# SCH_Esp32-Wroom-Air-suspension_2025-01-0.net
KiCad netlist of a schematic drawn in EasyEDA
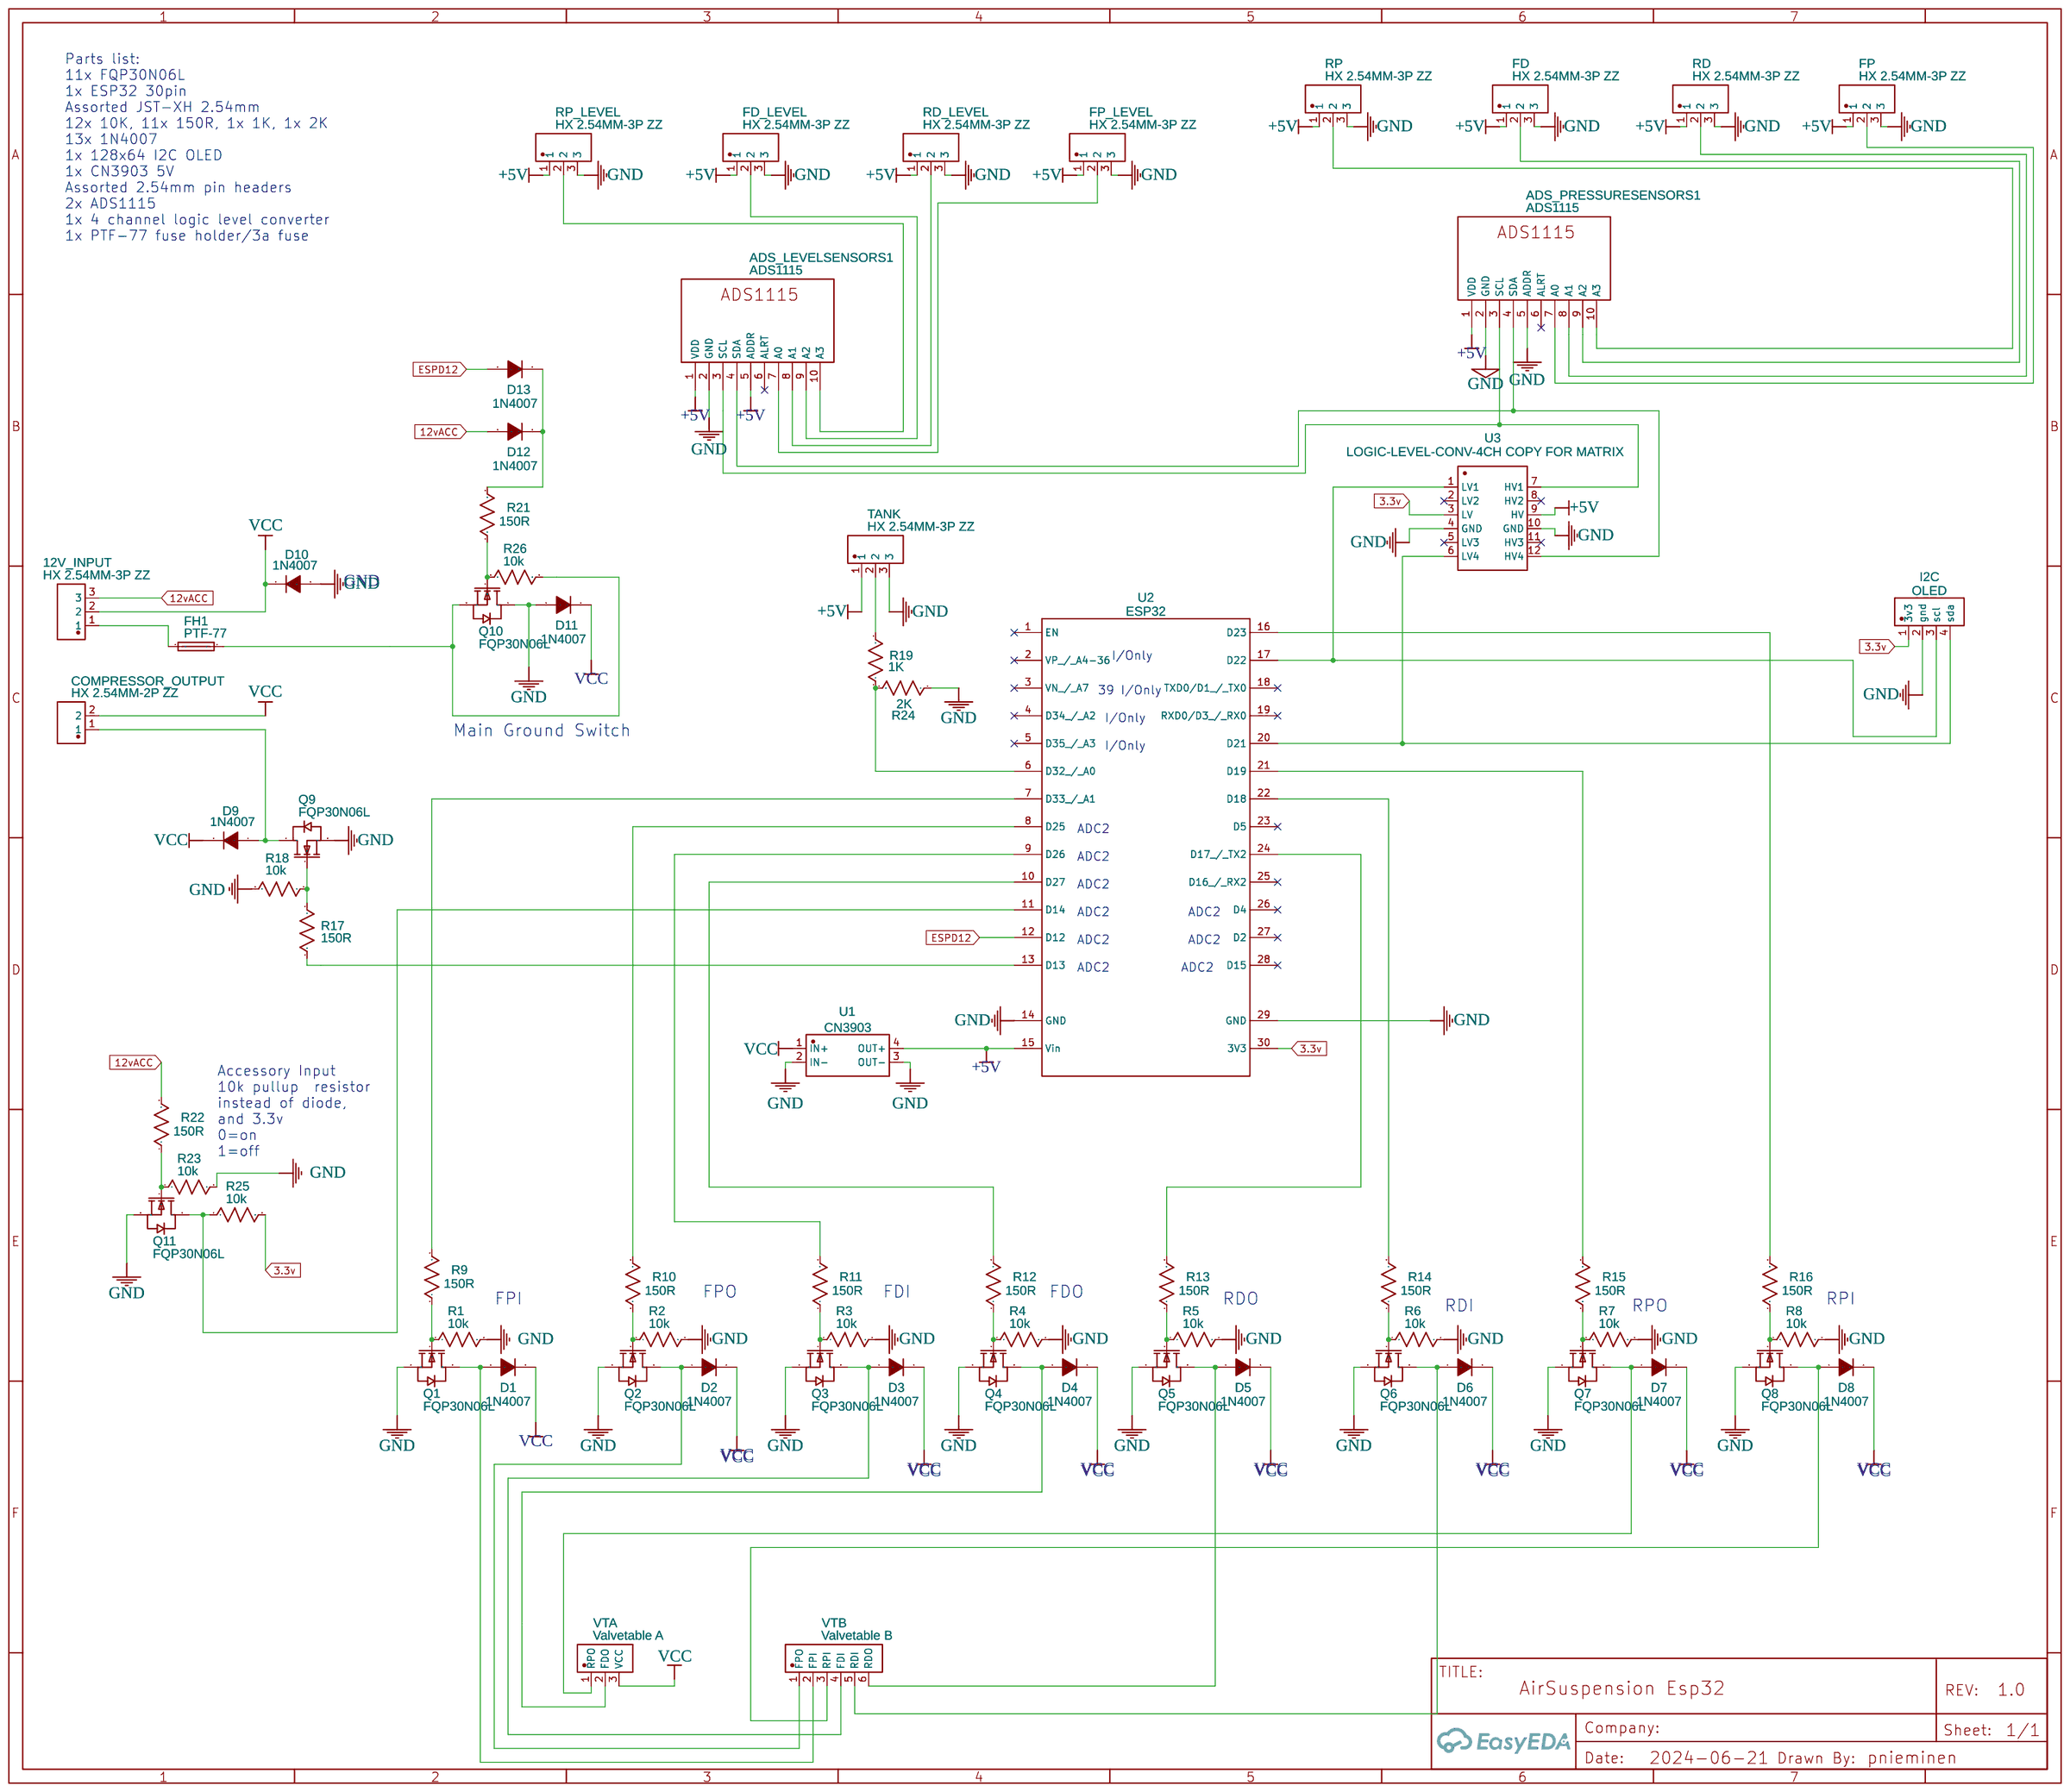
[diagram p0: schematic sheet]

(export (version "E")
  (design (tool "Eeschema 10.0.6"))
  (components
    (comp (ref "12V_INPUT")
      (value "HX 2.54MM-3P ZZ")
      (fields (field (name "Manufacturer Part") "HX 2.54mm-3P ZZ") (field (name "Manufacturer") "hanxia(韩下)"))
      (libsource (lib "") (part "HX 2.54MM-3P ZZ_9"))
    )
    (comp (ref "ADS_LEVELSENSORS1") (value "ADS1115") (libsource (lib "") (part "ADS1115_1")))
    (comp (ref "ADS_PRESSURESENSORS1") (value "ADS1115") (libsource (lib "") (part "ADS1115")))
    (comp (ref "COMPRESSOR_OUTPUT")
      (value "HX 2.54MM-2P ZZ")
      (fields (field (name "Manufacturer Part") "HX 2.54mm-2P ZZ") (field (name "Manufacturer") "hanxia(韩下)"))
      (libsource (lib "") (part "HX 2.54MM-2P ZZ"))
    )
    (comp (ref "D1")
      (value "1N4007")
      (fields (field (name "Manufacturer Part") "1N4007-E3/54") (field (name "Manufacturer") "VISHAY"))
      (libsource (lib "") (part "1N4007-E3/54"))
    )
    (comp (ref "D2")
      (value "1N4007")
      (fields (field (name "Manufacturer Part") "1N4007-E3/54") (field (name "Manufacturer") "VISHAY"))
      (libsource (lib "") (part "1N4007-E3/54"))
    )
    (comp (ref "D3")
      (value "1N4007")
      (fields (field (name "Manufacturer Part") "1N4007-E3/54") (field (name "Manufacturer") "VISHAY"))
      (libsource (lib "") (part "1N4007-E3/54"))
    )
    (comp (ref "D4")
      (value "1N4007")
      (fields (field (name "Manufacturer Part") "1N4007-E3/54") (field (name "Manufacturer") "VISHAY"))
      (libsource (lib "") (part "1N4007-E3/54"))
    )
    (comp (ref "D5")
      (value "1N4007")
      (fields (field (name "Manufacturer Part") "1N4007-E3/54") (field (name "Manufacturer") "VISHAY"))
      (libsource (lib "") (part "1N4007-E3/54"))
    )
    (comp (ref "D6")
      (value "1N4007")
      (fields (field (name "Manufacturer Part") "1N4007-E3/54") (field (name "Manufacturer") "VISHAY"))
      (libsource (lib "") (part "1N4007-E3/54"))
    )
    (comp (ref "D7")
      (value "1N4007")
      (fields (field (name "Manufacturer Part") "1N4007-E3/54") (field (name "Manufacturer") "VISHAY"))
      (libsource (lib "") (part "1N4007-E3/54"))
    )
    (comp (ref "D8")
      (value "1N4007")
      (fields (field (name "Manufacturer Part") "1N4007-E3/54") (field (name "Manufacturer") "VISHAY"))
      (libsource (lib "") (part "1N4007-E3/54"))
    )
    (comp (ref "D9")
      (value "1N4007")
      (fields (field (name "Manufacturer Part") "1N4007-E3/54") (field (name "Manufacturer") "VISHAY"))
      (libsource (lib "") (part "1N4007-E3/54_1"))
    )
    (comp (ref "D10")
      (value "1N4007")
      (fields (field (name "Manufacturer Part") "1N4007-E3/54") (field (name "Manufacturer") "VISHAY"))
      (libsource (lib "") (part "1N4007-E3/54_1"))
    )
    (comp (ref "D11")
      (value "1N4007")
      (fields (field (name "Manufacturer Part") "1N4007-E3/54") (field (name "Manufacturer") "VISHAY"))
      (libsource (lib "") (part "1N4007-E3/54"))
    )
    (comp (ref "D12")
      (value "1N4007")
      (fields (field (name "Manufacturer Part") "1N4007-E3/54") (field (name "Manufacturer") "VISHAY"))
      (libsource (lib "") (part "1N4007-E3/54"))
    )
    (comp (ref "D13")
      (value "1N4007")
      (fields (field (name "Manufacturer Part") "1N4007-E3/54") (field (name "Manufacturer") "VISHAY"))
      (libsource (lib "") (part "1N4007-E3/54"))
    )
    (comp (ref "FD")
      (value "HX 2.54MM-3P ZZ")
      (fields (field (name "Manufacturer Part") "HX 2.54mm-3P ZZ") (field (name "Manufacturer") "hanxia(韩下)"))
      (libsource (lib "") (part "HX 2.54MM-3P ZZ_3"))
    )
    (comp (ref "FD_LEVEL")
      (value "HX 2.54MM-3P ZZ")
      (fields (field (name "Manufacturer Part") "HX 2.54mm-3P ZZ") (field (name "Manufacturer") "hanxia(韩下)"))
      (libsource (lib "") (part "HX 2.54MM-3P ZZ_7"))
    )
    (comp (ref "FH1")
      (value "PTF-77")
      (fields (field (name "Manufacturer") "XFCN(兴飞)"))
      (libsource (lib "") (part "PTF-77"))
    )
    (comp (ref "FP")
      (value "HX 2.54MM-3P ZZ")
      (fields (field (name "Manufacturer Part") "HX 2.54mm-3P ZZ") (field (name "Manufacturer") "hanxia(韩下)"))
      (libsource (lib "") (part "HX 2.54MM-3P ZZ_1"))
    )
    (comp (ref "FP_LEVEL")
      (value "HX 2.54MM-3P ZZ")
      (fields (field (name "Manufacturer Part") "HX 2.54mm-3P ZZ") (field (name "Manufacturer") "hanxia(韩下)"))
      (libsource (lib "") (part "HX 2.54MM-3P ZZ_5"))
    )
    (comp (ref "OLED")
      (value "I2C")
      (fields (field (name "Manufacturer Part") "HX 2.54mm-4P ZZ") (field (name "Manufacturer") "hanxia(韩下)"))
      (libsource (lib "") (part "HX 2.54MM-4P ZZ"))
    )
    (comp (ref "Q1")
      (value "FQP30N06L")
      (fields (field (name "Manufacturer Part") "FQP30N06L-VB") (field (name "Manufacturer") "VBsemi(微碧半导体)"))
      (libsource (lib "") (part "FQP30N06L"))
    )
    (comp (ref "Q2")
      (value "FQP30N06L")
      (fields (field (name "Manufacturer Part") "FQP30N06L-VB") (field (name "Manufacturer") "VBsemi(微碧半导体)"))
      (libsource (lib "") (part "FQP30N06L"))
    )
    (comp (ref "Q3")
      (value "FQP30N06L")
      (fields (field (name "Manufacturer Part") "FQP30N06L-VB") (field (name "Manufacturer") "VBsemi(微碧半导体)"))
      (libsource (lib "") (part "FQP30N06L"))
    )
    (comp (ref "Q4")
      (value "FQP30N06L")
      (fields (field (name "Manufacturer Part") "FQP30N06L-VB") (field (name "Manufacturer") "VBsemi(微碧半导体)"))
      (libsource (lib "") (part "FQP30N06L"))
    )
    (comp (ref "Q5")
      (value "FQP30N06L")
      (fields (field (name "Manufacturer Part") "FQP30N06L-VB") (field (name "Manufacturer") "VBsemi(微碧半导体)"))
      (libsource (lib "") (part "FQP30N06L"))
    )
    (comp (ref "Q6")
      (value "FQP30N06L")
      (fields (field (name "Manufacturer Part") "FQP30N06L-VB") (field (name "Manufacturer") "VBsemi(微碧半导体)"))
      (libsource (lib "") (part "FQP30N06L"))
    )
    (comp (ref "Q7")
      (value "FQP30N06L")
      (fields (field (name "Manufacturer Part") "FQP30N06L-VB") (field (name "Manufacturer") "VBsemi(微碧半导体)"))
      (libsource (lib "") (part "FQP30N06L"))
    )
    (comp (ref "Q8")
      (value "FQP30N06L")
      (fields (field (name "Manufacturer Part") "FQP30N06L-VB") (field (name "Manufacturer") "VBsemi(微碧半导体)"))
      (libsource (lib "") (part "FQP30N06L"))
    )
    (comp (ref "Q9")
      (value "FQP30N06L")
      (fields (field (name "Manufacturer Part") "FQP30N06L-VB") (field (name "Manufacturer") "VBsemi(微碧半导体)"))
      (libsource (lib "") (part "FQP30N06L_1"))
    )
    (comp (ref "Q10")
      (value "FQP30N06L")
      (fields (field (name "Manufacturer Part") "FQP30N06L-VB") (field (name "Manufacturer") "VBsemi(微碧半导体)"))
      (libsource (lib "") (part "FQP30N06L"))
    )
    (comp (ref "Q11")
      (value "FQP30N06L")
      (fields (field (name "Manufacturer Part") "FQP30N06L-VB") (field (name "Manufacturer") "VBsemi(微碧半导体)"))
      (libsource (lib "") (part "FQP30N06L"))
    )
    (comp (ref "R1") (value "10k") (libsource (lib "") (part "R_AXIAL-1.0_US_1")))
    (comp (ref "R2") (value "10k") (libsource (lib "") (part "R_AXIAL-1.0_US_1")))
    (comp (ref "R3") (value "10k") (libsource (lib "") (part "R_AXIAL-1.0_US_1")))
    (comp (ref "R4") (value "10k") (libsource (lib "") (part "R_AXIAL-1.0_US_1")))
    (comp (ref "R5") (value "10k") (libsource (lib "") (part "R_AXIAL-1.0_US_1")))
    (comp (ref "R6") (value "10k") (libsource (lib "") (part "R_AXIAL-1.0_US_1")))
    (comp (ref "R7") (value "10k") (libsource (lib "") (part "R_AXIAL-1.0_US_1")))
    (comp (ref "R8") (value "10k") (libsource (lib "") (part "R_AXIAL-1.0_US_1")))
    (comp (ref "R9") (value "150R") (libsource (lib "") (part "R_AXIAL-1.0_US")))
    (comp (ref "R10") (value "150R") (libsource (lib "") (part "R_AXIAL-1.0_US")))
    (comp (ref "R11") (value "150R") (libsource (lib "") (part "R_AXIAL-1.0_US")))
    (comp (ref "R12") (value "150R") (libsource (lib "") (part "R_AXIAL-1.0_US")))
    (comp (ref "R13") (value "150R") (libsource (lib "") (part "R_AXIAL-1.0_US")))
    (comp (ref "R14") (value "150R") (libsource (lib "") (part "R_AXIAL-1.0_US")))
    (comp (ref "R15") (value "150R") (libsource (lib "") (part "R_AXIAL-1.0_US")))
    (comp (ref "R16") (value "150R") (libsource (lib "") (part "R_AXIAL-1.0_US")))
    (comp (ref "R17") (value "150R") (libsource (lib "") (part "R_AXIAL-1.0_US_3")))
    (comp (ref "R18") (value "10k") (libsource (lib "") (part "R_AXIAL-1.0_US_2")))
    (comp (ref "R19") (value "1K") (libsource (lib "") (part "R_AXIAL-1.0_US")))
    (comp (ref "R21") (value "150R") (libsource (lib "") (part "R_AXIAL-1.0_US")))
    (comp (ref "R22") (value "150R") (libsource (lib "") (part "R_AXIAL-1.0_US")))
    (comp (ref "R23") (value "10k") (libsource (lib "") (part "R_AXIAL-1.0_US_1")))
    (comp (ref "R24") (value "2K") (libsource (lib "") (part "R_AXIAL-1.0_US_2")))
    (comp (ref "R25") (value "10k") (libsource (lib "") (part "R_AXIAL-1.0_US_1")))
    (comp (ref "R26") (value "10k") (libsource (lib "") (part "R_AXIAL-1.0_US_1")))
    (comp (ref "RD")
      (value "HX 2.54MM-3P ZZ")
      (fields (field (name "Manufacturer Part") "HX 2.54mm-3P ZZ") (field (name "Manufacturer") "hanxia(韩下)"))
      (libsource (lib "") (part "HX 2.54MM-3P ZZ"))
    )
    (comp (ref "RD_LEVEL")
      (value "HX 2.54MM-3P ZZ")
      (fields (field (name "Manufacturer Part") "HX 2.54mm-3P ZZ") (field (name "Manufacturer") "hanxia(韩下)"))
      (libsource (lib "") (part "HX 2.54MM-3P ZZ_8"))
    )
    (comp (ref "RP")
      (value "HX 2.54MM-3P ZZ")
      (fields (field (name "Manufacturer Part") "HX 2.54mm-3P ZZ") (field (name "Manufacturer") "hanxia(韩下)"))
      (libsource (lib "") (part "HX 2.54MM-3P ZZ_6"))
    )
    (comp (ref "RP_LEVEL")
      (value "HX 2.54MM-3P ZZ")
      (fields (field (name "Manufacturer Part") "HX 2.54mm-3P ZZ") (field (name "Manufacturer") "hanxia(韩下)"))
      (libsource (lib "") (part "HX 2.54MM-3P ZZ_10"))
    )
    (comp (ref "TANK")
      (value "HX 2.54MM-3P ZZ")
      (fields (field (name "Manufacturer Part") "HX 2.54mm-3P ZZ") (field (name "Manufacturer") "hanxia(韩下)"))
      (libsource (lib "") (part "HX 2.54MM-3P ZZ_2"))
    )
    (comp (ref "U1") (value "CN3903") (libsource (lib "") (part "CN3903-DCDC-STEPDOWN-3V3")))
    (comp (ref "U2")
      (value "ESP32")
      (fields
        (field (name "Manufacturer Part") "ESP32WROOM32")
        (field (name "Manufacturer") "Espressif Systems")
      )
      (libsource (lib "") (part "ESP32"))
    )
    (comp (ref "U3")
      (value "LOGIC-LEVEL-CONV-4CH COPY FOR MATRIX")
      (fields (field (name "Manufacturer Part") "Level Converter 4"))
      (libsource (lib "") (part "LOGIC-LEVEL-CONV-4CH COPY FOR MATRIX"))
    )
    (comp (ref "VTA")
      (value "Valvetable A")
      (fields (field (name "Manufacturer Part") "HX 2.54mm-3P ZZ") (field (name "Manufacturer") "hanxia(韩下)"))
      (libsource (lib "") (part "HX 2.54MM-3P ZZ_4"))
    )
    (comp (ref "VTB")
      (value "Valvetable B")
      (fields (field (name "Manufacturer Part") "HX 2.54mm-6P ZZ") (field (name "Manufacturer") "hanxia(韩下)"))
      (libsource (lib "") (part "HX 2.54MM-6P ZZ"))
    )
  )
  (nets
    (net (code "1") (name "+5V") (class "Default")
      (node (ref "ADS_LEVELSENSORS1") (pin "1") (pinfunction "VDD_1") (pintype "unspecified"))
      (node (ref "ADS_LEVELSENSORS1") (pin "5") (pinfunction "ADDR_5") (pintype "unspecified"))
      (node (ref "ADS_PRESSURESENSORS1") (pin "1") (pinfunction "VDD_1") (pintype "unspecified"))
      (node (ref "FD") (pin "1") (pinfunction "1_1") (pintype "unspecified"))
      (node (ref "FD_LEVEL") (pin "1") (pinfunction "1_1") (pintype "unspecified"))
      (node (ref "FP") (pin "1") (pinfunction "1_1") (pintype "unspecified"))
      (node (ref "FP_LEVEL") (pin "1") (pinfunction "1_1") (pintype "unspecified"))
      (node (ref "RD") (pin "1") (pinfunction "1_1") (pintype "unspecified"))
      (node (ref "RD_LEVEL") (pin "1") (pinfunction "1_1") (pintype "unspecified"))
      (node (ref "RP") (pin "1") (pinfunction "1_1") (pintype "unspecified"))
      (node (ref "RP_LEVEL") (pin "1") (pinfunction "1_1") (pintype "unspecified"))
      (node (ref "TANK") (pin "1") (pinfunction "1_1") (pintype "unspecified"))
      (node (ref "U1") (pin "4") (pinfunction "OUT+_4") (pintype "unspecified"))
      (node (ref "U2") (pin "15") (pinfunction "Vin_15") (pintype "unspecified"))
      (node (ref "U3") (pin "9") (pinfunction "HV_9") (pintype "unspecified"))
    )
    (net (code "2") (name "3.3v") (class "Default")
      (node (ref "OLED") (pin "1") (pinfunction "3v3_1") (pintype "unspecified"))
      (node (ref "R25") (pin "2") (pinfunction "2_2") (pintype "unspecified"))
      (node (ref "U2") (pin "30") (pinfunction "3V3_30") (pintype "unspecified"))
      (node (ref "U3") (pin "3") (pinfunction "LV_3") (pintype "unspecified"))
    )
    (net (code "3") (name "12vACC") (class "Default")
      (node (ref "12V_INPUT") (pin "3") (pinfunction "3_3") (pintype "unspecified"))
      (node (ref "D12") (pin "1") (pinfunction "A_1") (pintype "unspecified"))
      (node (ref "R22") (pin "2") (pinfunction "2_2") (pintype "unspecified"))
    )
    (net (code "4") (name "ESPD12") (class "Default")
      (node (ref "D13") (pin "1") (pinfunction "A_1") (pintype "unspecified"))
      (node (ref "U2") (pin "12") (pinfunction "D12_12") (pintype "unspecified"))
    )
    (net (code "5") (name "GND") (class "Default")
      (node (ref "ADS_LEVELSENSORS1") (pin "2") (pinfunction "GND_2") (pintype "unspecified"))
      (node (ref "ADS_PRESSURESENSORS1") (pin "2") (pinfunction "GND_2") (pintype "unspecified"))
      (node (ref "ADS_PRESSURESENSORS1") (pin "5") (pinfunction "ADDR_5") (pintype "unspecified"))
      (node (ref "D10") (pin "1") (pinfunction "A_1") (pintype "unspecified"))
      (node (ref "D11") (pin "1") (pinfunction "A_1") (pintype "unspecified"))
      (node (ref "FD") (pin "3") (pinfunction "3_3") (pintype "unspecified"))
      (node (ref "FD_LEVEL") (pin "3") (pinfunction "3_3") (pintype "unspecified"))
      (node (ref "FP") (pin "3") (pinfunction "3_3") (pintype "unspecified"))
      (node (ref "FP_LEVEL") (pin "3") (pinfunction "3_3") (pintype "unspecified"))
      (node (ref "OLED") (pin "2") (pinfunction "gnd_2") (pintype "unspecified"))
      (node (ref "Q1") (pin "3") (pinfunction "S_3") (pintype "unspecified"))
      (node (ref "Q10") (pin "2") (pinfunction "D_2") (pintype "unspecified"))
      (node (ref "Q11") (pin "3") (pinfunction "S_3") (pintype "unspecified"))
      (node (ref "Q2") (pin "3") (pinfunction "S_3") (pintype "unspecified"))
      (node (ref "Q3") (pin "3") (pinfunction "S_3") (pintype "unspecified"))
      (node (ref "Q4") (pin "3") (pinfunction "S_3") (pintype "unspecified"))
      (node (ref "Q5") (pin "3") (pinfunction "S_3") (pintype "unspecified"))
      (node (ref "Q6") (pin "3") (pinfunction "S_3") (pintype "unspecified"))
      (node (ref "Q7") (pin "3") (pinfunction "S_3") (pintype "unspecified"))
      (node (ref "Q8") (pin "3") (pinfunction "S_3") (pintype "unspecified"))
      (node (ref "Q9") (pin "3") (pinfunction "S_3") (pintype "unspecified"))
      (node (ref "R1") (pin "2") (pinfunction "2_2") (pintype "unspecified"))
      (node (ref "R18") (pin "2") (pinfunction "2_2") (pintype "unspecified"))
      (node (ref "R2") (pin "2") (pinfunction "2_2") (pintype "unspecified"))
      (node (ref "R23") (pin "2") (pinfunction "2_2") (pintype "unspecified"))
      (node (ref "R24") (pin "1") (pinfunction "1_1") (pintype "unspecified"))
      (node (ref "R3") (pin "2") (pinfunction "2_2") (pintype "unspecified"))
      (node (ref "R4") (pin "2") (pinfunction "2_2") (pintype "unspecified"))
      (node (ref "R5") (pin "2") (pinfunction "2_2") (pintype "unspecified"))
      (node (ref "R6") (pin "2") (pinfunction "2_2") (pintype "unspecified"))
      (node (ref "R7") (pin "2") (pinfunction "2_2") (pintype "unspecified"))
      (node (ref "R8") (pin "2") (pinfunction "2_2") (pintype "unspecified"))
      (node (ref "RD") (pin "3") (pinfunction "3_3") (pintype "unspecified"))
      (node (ref "RD_LEVEL") (pin "3") (pinfunction "3_3") (pintype "unspecified"))
      (node (ref "RP") (pin "3") (pinfunction "3_3") (pintype "unspecified"))
      (node (ref "RP_LEVEL") (pin "3") (pinfunction "3_3") (pintype "unspecified"))
      (node (ref "TANK") (pin "3") (pinfunction "3_3") (pintype "unspecified"))
      (node (ref "U1") (pin "2") (pinfunction "IN-_2") (pintype "unspecified"))
      (node (ref "U1") (pin "3") (pinfunction "OUT-_3") (pintype "unspecified"))
      (node (ref "U2") (pin "14") (pinfunction "GND_14") (pintype "unspecified"))
      (node (ref "U2") (pin "29") (pinfunction "GND_29") (pintype "unspecified"))
      (node (ref "U3") (pin "10") (pinfunction "GND_10") (pintype "unspecified"))
      (node (ref "U3") (pin "4") (pinfunction "GND_4") (pintype "unspecified"))
    )
    (net (code "6") (name "Net-(12V_INPUT-Pad1)") (class "Default")
      (node (ref "12V_INPUT") (pin "1") (pinfunction "1_1") (pintype "unspecified"))
      (node (ref "FH1") (pin "1") (pinfunction "1_1") (pintype "unspecified"))
    )
    (net (code "7") (name "Net-(ADS_LEVELSENSORS1-A0)") (class "Default")
      (node (ref "ADS_LEVELSENSORS1") (pin "7") (pinfunction "A0_7") (pintype "unspecified"))
      (node (ref "FP_LEVEL") (pin "2") (pinfunction "2_2") (pintype "unspecified"))
    )
    (net (code "8") (name "Net-(ADS_LEVELSENSORS1-A1)") (class "Default")
      (node (ref "ADS_LEVELSENSORS1") (pin "8") (pinfunction "A1_8") (pintype "unspecified"))
      (node (ref "RD_LEVEL") (pin "2") (pinfunction "2_2") (pintype "unspecified"))
    )
    (net (code "9") (name "Net-(ADS_LEVELSENSORS1-A2)") (class "Default")
      (node (ref "ADS_LEVELSENSORS1") (pin "9") (pinfunction "A2_9") (pintype "unspecified"))
      (node (ref "FD_LEVEL") (pin "2") (pinfunction "2_2") (pintype "unspecified"))
    )
    (net (code "10") (name "Net-(ADS_LEVELSENSORS1-A3)") (class "Default")
      (node (ref "ADS_LEVELSENSORS1") (pin "10") (pinfunction "A3_10") (pintype "unspecified"))
      (node (ref "RP_LEVEL") (pin "2") (pinfunction "2_2") (pintype "unspecified"))
    )
    (net (code "11") (name "Net-(ADS_LEVELSENSORS1-SCL)") (class "Default")
      (node (ref "ADS_LEVELSENSORS1") (pin "3") (pinfunction "SCL_3") (pintype "unspecified"))
      (node (ref "ADS_PRESSURESENSORS1") (pin "3") (pinfunction "SCL_3") (pintype "unspecified"))
      (node (ref "U3") (pin "7") (pinfunction "HV1_7") (pintype "unspecified"))
    )
    (net (code "12") (name "Net-(ADS_LEVELSENSORS1-SDA)") (class "Default")
      (node (ref "ADS_LEVELSENSORS1") (pin "4") (pinfunction "SDA_4") (pintype "unspecified"))
      (node (ref "ADS_PRESSURESENSORS1") (pin "4") (pinfunction "SDA_4") (pintype "unspecified"))
      (node (ref "U3") (pin "12") (pinfunction "HV4_12") (pintype "unspecified"))
    )
    (net (code "13") (name "Net-(ADS_PRESSURESENSORS1-A0)") (class "Default")
      (node (ref "ADS_PRESSURESENSORS1") (pin "7") (pinfunction "A0_7") (pintype "unspecified"))
      (node (ref "FP") (pin "2") (pinfunction "2_2") (pintype "unspecified"))
    )
    (net (code "14") (name "Net-(ADS_PRESSURESENSORS1-A1)") (class "Default")
      (node (ref "ADS_PRESSURESENSORS1") (pin "8") (pinfunction "A1_8") (pintype "unspecified"))
      (node (ref "RD") (pin "2") (pinfunction "2_2") (pintype "unspecified"))
    )
    (net (code "15") (name "Net-(ADS_PRESSURESENSORS1-A2)") (class "Default")
      (node (ref "ADS_PRESSURESENSORS1") (pin "9") (pinfunction "A2_9") (pintype "unspecified"))
      (node (ref "FD") (pin "2") (pinfunction "2_2") (pintype "unspecified"))
    )
    (net (code "16") (name "Net-(ADS_PRESSURESENSORS1-A3)") (class "Default")
      (node (ref "ADS_PRESSURESENSORS1") (pin "10") (pinfunction "A3_10") (pintype "unspecified"))
      (node (ref "RP") (pin "2") (pinfunction "2_2") (pintype "unspecified"))
    )
    (net (code "17") (name "Net-(D1-A)") (class "Default")
      (node (ref "D1") (pin "1") (pinfunction "A_1") (pintype "unspecified"))
      (node (ref "Q1") (pin "2") (pinfunction "D_2") (pintype "unspecified"))
      (node (ref "VTB") (pin "2") (pinfunction "FPI_2") (pintype "unspecified"))
    )
    (net (code "18") (name "Net-(D2-A)") (class "Default")
      (node (ref "D2") (pin "1") (pinfunction "A_1") (pintype "unspecified"))
      (node (ref "Q2") (pin "2") (pinfunction "D_2") (pintype "unspecified"))
      (node (ref "VTB") (pin "1") (pinfunction "FPO_1") (pintype "unspecified"))
    )
    (net (code "19") (name "Net-(D3-A)") (class "Default")
      (node (ref "D3") (pin "1") (pinfunction "A_1") (pintype "unspecified"))
      (node (ref "Q3") (pin "2") (pinfunction "D_2") (pintype "unspecified"))
      (node (ref "VTB") (pin "4") (pinfunction "FDI_4") (pintype "unspecified"))
    )
    (net (code "20") (name "Net-(D4-A)") (class "Default")
      (node (ref "D4") (pin "1") (pinfunction "A_1") (pintype "unspecified"))
      (node (ref "Q4") (pin "2") (pinfunction "D_2") (pintype "unspecified"))
      (node (ref "VTA") (pin "2") (pinfunction "FDO_2") (pintype "unspecified"))
    )
    (net (code "21") (name "Net-(D5-A)") (class "Default")
      (node (ref "D5") (pin "1") (pinfunction "A_1") (pintype "unspecified"))
      (node (ref "Q5") (pin "2") (pinfunction "D_2") (pintype "unspecified"))
      (node (ref "VTB") (pin "6") (pinfunction "RDO_6") (pintype "unspecified"))
    )
    (net (code "22") (name "Net-(D6-A)") (class "Default")
      (node (ref "D6") (pin "1") (pinfunction "A_1") (pintype "unspecified"))
      (node (ref "Q6") (pin "2") (pinfunction "D_2") (pintype "unspecified"))
      (node (ref "VTB") (pin "5") (pinfunction "RDI_5") (pintype "unspecified"))
    )
    (net (code "23") (name "Net-(D7-A)") (class "Default")
      (node (ref "D7") (pin "1") (pinfunction "A_1") (pintype "unspecified"))
      (node (ref "Q7") (pin "2") (pinfunction "D_2") (pintype "unspecified"))
      (node (ref "VTA") (pin "1") (pinfunction "RPO_1") (pintype "unspecified"))
    )
    (net (code "24") (name "Net-(D8-A)") (class "Default")
      (node (ref "D8") (pin "1") (pinfunction "A_1") (pintype "unspecified"))
      (node (ref "Q8") (pin "2") (pinfunction "D_2") (pintype "unspecified"))
      (node (ref "VTB") (pin "3") (pinfunction "RPI_3") (pintype "unspecified"))
    )
    (net (code "25") (name "Net-(D9-A)") (class "Default")
      (node (ref "COMPRESSOR_OUTPUT") (pin "1") (pinfunction "1_1") (pintype "unspecified"))
      (node (ref "D9") (pin "1") (pinfunction "A_1") (pintype "unspecified"))
      (node (ref "Q9") (pin "2") (pinfunction "D_2") (pintype "unspecified"))
    )
    (net (code "26") (name "Net-(D12-K)") (class "Default")
      (node (ref "D12") (pin "2") (pinfunction "K_2") (pintype "unspecified"))
      (node (ref "D13") (pin "2") (pinfunction "K_2") (pintype "unspecified"))
      (node (ref "R21") (pin "2") (pinfunction "2_2") (pintype "unspecified"))
    )
    (net (code "27") (name "Net-(OLED-scl)") (class "Default")
      (node (ref "OLED") (pin "3") (pinfunction "scl_3") (pintype "unspecified"))
      (node (ref "U2") (pin "17") (pinfunction "D22_17") (pintype "unspecified"))
      (node (ref "U3") (pin "1") (pinfunction "LV1_1") (pintype "unspecified"))
    )
    (net (code "28") (name "Net-(OLED-sda)") (class "Default")
      (node (ref "OLED") (pin "4") (pinfunction "sda_4") (pintype "unspecified"))
      (node (ref "U2") (pin "20") (pinfunction "D21_20") (pintype "unspecified"))
      (node (ref "U3") (pin "6") (pinfunction "LV4_6") (pintype "unspecified"))
    )
    (net (code "29") (name "Net-(Q1-G)") (class "Default")
      (node (ref "Q1") (pin "1") (pinfunction "G_1") (pintype "unspecified"))
      (node (ref "R1") (pin "1") (pinfunction "1_1") (pintype "unspecified"))
      (node (ref "R9") (pin "1") (pinfunction "1_1") (pintype "unspecified"))
    )
    (net (code "30") (name "Net-(Q2-G)") (class "Default")
      (node (ref "Q2") (pin "1") (pinfunction "G_1") (pintype "unspecified"))
      (node (ref "R10") (pin "1") (pinfunction "1_1") (pintype "unspecified"))
      (node (ref "R2") (pin "1") (pinfunction "1_1") (pintype "unspecified"))
    )
    (net (code "31") (name "Net-(Q3-G)") (class "Default")
      (node (ref "Q3") (pin "1") (pinfunction "G_1") (pintype "unspecified"))
      (node (ref "R11") (pin "1") (pinfunction "1_1") (pintype "unspecified"))
      (node (ref "R3") (pin "1") (pinfunction "1_1") (pintype "unspecified"))
    )
    (net (code "32") (name "Net-(Q4-G)") (class "Default")
      (node (ref "Q4") (pin "1") (pinfunction "G_1") (pintype "unspecified"))
      (node (ref "R12") (pin "1") (pinfunction "1_1") (pintype "unspecified"))
      (node (ref "R4") (pin "1") (pinfunction "1_1") (pintype "unspecified"))
    )
    (net (code "33") (name "Net-(Q5-G)") (class "Default")
      (node (ref "Q5") (pin "1") (pinfunction "G_1") (pintype "unspecified"))
      (node (ref "R13") (pin "1") (pinfunction "1_1") (pintype "unspecified"))
      (node (ref "R5") (pin "1") (pinfunction "1_1") (pintype "unspecified"))
    )
    (net (code "34") (name "Net-(Q6-G)") (class "Default")
      (node (ref "Q6") (pin "1") (pinfunction "G_1") (pintype "unspecified"))
      (node (ref "R14") (pin "1") (pinfunction "1_1") (pintype "unspecified"))
      (node (ref "R6") (pin "1") (pinfunction "1_1") (pintype "unspecified"))
    )
    (net (code "35") (name "Net-(Q7-G)") (class "Default")
      (node (ref "Q7") (pin "1") (pinfunction "G_1") (pintype "unspecified"))
      (node (ref "R15") (pin "1") (pinfunction "1_1") (pintype "unspecified"))
      (node (ref "R7") (pin "1") (pinfunction "1_1") (pintype "unspecified"))
    )
    (net (code "36") (name "Net-(Q8-G)") (class "Default")
      (node (ref "Q8") (pin "1") (pinfunction "G_1") (pintype "unspecified"))
      (node (ref "R16") (pin "1") (pinfunction "1_1") (pintype "unspecified"))
      (node (ref "R8") (pin "1") (pinfunction "1_1") (pintype "unspecified"))
    )
    (net (code "37") (name "Net-(Q9-G)") (class "Default")
      (node (ref "Q9") (pin "1") (pinfunction "G_1") (pintype "unspecified"))
      (node (ref "R17") (pin "1") (pinfunction "1_1") (pintype "unspecified"))
      (node (ref "R18") (pin "1") (pinfunction "1_1") (pintype "unspecified"))
    )
    (net (code "38") (name "Net-(Q10-G)") (class "Default")
      (node (ref "Q10") (pin "1") (pinfunction "G_1") (pintype "unspecified"))
      (node (ref "R21") (pin "1") (pinfunction "1_1") (pintype "unspecified"))
      (node (ref "R26") (pin "1") (pinfunction "1_1") (pintype "unspecified"))
    )
    (net (code "39") (name "Net-(Q10-S)") (class "Default")
      (node (ref "FH1") (pin "2") (pinfunction "2_2") (pintype "unspecified"))
      (node (ref "Q10") (pin "3") (pinfunction "S_3") (pintype "unspecified"))
      (node (ref "R26") (pin "2") (pinfunction "2_2") (pintype "unspecified"))
    )
    (net (code "40") (name "Net-(Q11-D)") (class "Default")
      (node (ref "Q11") (pin "2") (pinfunction "D_2") (pintype "unspecified"))
      (node (ref "R25") (pin "1") (pinfunction "1_1") (pintype "unspecified"))
      (node (ref "U2") (pin "11") (pinfunction "D14_11") (pintype "unspecified"))
    )
    (net (code "41") (name "Net-(Q11-G)") (class "Default")
      (node (ref "Q11") (pin "1") (pinfunction "G_1") (pintype "unspecified"))
      (node (ref "R22") (pin "1") (pinfunction "1_1") (pintype "unspecified"))
      (node (ref "R23") (pin "1") (pinfunction "1_1") (pintype "unspecified"))
    )
    (net (code "42") (name "Net-(R19-Pad2)") (class "Default")
      (node (ref "R19") (pin "2") (pinfunction "2_2") (pintype "unspecified"))
      (node (ref "TANK") (pin "2") (pinfunction "2_2") (pintype "unspecified"))
    )
    (net (code "43") (name "Net-(U2-D13)") (class "Default")
      (node (ref "R17") (pin "2") (pinfunction "2_2") (pintype "unspecified"))
      (node (ref "U2") (pin "13") (pinfunction "D13_13") (pintype "unspecified"))
    )
    (net (code "44") (name "Net-(U2-D17_{slash}_TX2)") (class "Default")
      (node (ref "R13") (pin "2") (pinfunction "2_2") (pintype "unspecified"))
      (node (ref "U2") (pin "24") (pinfunction "D17_/_TX2_24") (pintype "unspecified"))
    )
    (net (code "45") (name "Net-(U2-D18)") (class "Default")
      (node (ref "R14") (pin "2") (pinfunction "2_2") (pintype "unspecified"))
      (node (ref "U2") (pin "22") (pinfunction "D18_22") (pintype "unspecified"))
    )
    (net (code "46") (name "Net-(U2-D19)") (class "Default")
      (node (ref "R15") (pin "2") (pinfunction "2_2") (pintype "unspecified"))
      (node (ref "U2") (pin "21") (pinfunction "D19_21") (pintype "unspecified"))
    )
    (net (code "47") (name "Net-(U2-D23)") (class "Default")
      (node (ref "R16") (pin "2") (pinfunction "2_2") (pintype "unspecified"))
      (node (ref "U2") (pin "16") (pinfunction "D23_16") (pintype "unspecified"))
    )
    (net (code "48") (name "Net-(U2-D25)") (class "Default")
      (node (ref "R10") (pin "2") (pinfunction "2_2") (pintype "unspecified"))
      (node (ref "U2") (pin "8") (pinfunction "D25_8") (pintype "unspecified"))
    )
    (net (code "49") (name "Net-(U2-D26)") (class "Default")
      (node (ref "R11") (pin "2") (pinfunction "2_2") (pintype "unspecified"))
      (node (ref "U2") (pin "9") (pinfunction "D26_9") (pintype "unspecified"))
    )
    (net (code "50") (name "Net-(U2-D27)") (class "Default")
      (node (ref "R12") (pin "2") (pinfunction "2_2") (pintype "unspecified"))
      (node (ref "U2") (pin "10") (pinfunction "D27_10") (pintype "unspecified"))
    )
    (net (code "51") (name "Net-(U2-D32_{slash}_A0)") (class "Default")
      (node (ref "R19") (pin "1") (pinfunction "1_1") (pintype "unspecified"))
      (node (ref "R24") (pin "2") (pinfunction "2_2") (pintype "unspecified"))
      (node (ref "U2") (pin "6") (pinfunction "D32_/_A0_6") (pintype "unspecified"))
    )
    (net (code "52") (name "Net-(U2-D33_{slash}_A1)") (class "Default")
      (node (ref "R9") (pin "2") (pinfunction "2_2") (pintype "unspecified"))
      (node (ref "U2") (pin "7") (pinfunction "D33_/_A1_7") (pintype "unspecified"))
    )
    (net (code "53") (name "VCC") (class "Default")
      (node (ref "12V_INPUT") (pin "2") (pinfunction "2_2") (pintype "unspecified"))
      (node (ref "COMPRESSOR_OUTPUT") (pin "2") (pinfunction "2_2") (pintype "unspecified"))
      (node (ref "D1") (pin "2") (pinfunction "K_2") (pintype "unspecified"))
      (node (ref "D10") (pin "2") (pinfunction "K_2") (pintype "unspecified"))
      (node (ref "D11") (pin "2") (pinfunction "K_2") (pintype "unspecified"))
      (node (ref "D2") (pin "2") (pinfunction "K_2") (pintype "unspecified"))
      (node (ref "D3") (pin "2") (pinfunction "K_2") (pintype "unspecified"))
      (node (ref "D4") (pin "2") (pinfunction "K_2") (pintype "unspecified"))
      (node (ref "D5") (pin "2") (pinfunction "K_2") (pintype "unspecified"))
      (node (ref "D6") (pin "2") (pinfunction "K_2") (pintype "unspecified"))
      (node (ref "D7") (pin "2") (pinfunction "K_2") (pintype "unspecified"))
      (node (ref "D8") (pin "2") (pinfunction "K_2") (pintype "unspecified"))
      (node (ref "D9") (pin "2") (pinfunction "K_2") (pintype "unspecified"))
      (node (ref "U1") (pin "1") (pinfunction "IN+_1") (pintype "unspecified"))
      (node (ref "VTA") (pin "3") (pinfunction "VCC_3") (pintype "unspecified"))
    )
    (net (code "54") (name "unconnected-(ADS_LEVELSENSORS1-ALRT-Pad6)") (class "Default")
      (node (ref "ADS_LEVELSENSORS1") (pin "6") (pinfunction "ALRT_6") (pintype "unspecified+no_connect"))
    )
    (net (code "55") (name "unconnected-(ADS_PRESSURESENSORS1-ALRT-Pad6)") (class "Default")
      (node (ref "ADS_PRESSURESENSORS1") (pin "6") (pinfunction "ALRT_6") (pintype "unspecified+no_connect"))
    )
    (net (code "56") (name "unconnected-(U2-D2-Pad27)") (class "Default")
      (node (ref "U2") (pin "27") (pinfunction "D2_27") (pintype "unspecified+no_connect"))
    )
    (net (code "57") (name "unconnected-(U2-D4-Pad26)") (class "Default")
      (node (ref "U2") (pin "26") (pinfunction "D4_26") (pintype "unspecified+no_connect"))
    )
    (net (code "58") (name "unconnected-(U2-D5-Pad23)") (class "Default")
      (node (ref "U2") (pin "23") (pinfunction "D5_23") (pintype "unspecified+no_connect"))
    )
    (net (code "59") (name "unconnected-(U2-D15-Pad28)") (class "Default")
      (node (ref "U2") (pin "28") (pinfunction "D15_28") (pintype "unspecified+no_connect"))
    )
    (net (code "60") (name "unconnected-(U2-D16_{slash}_RX2-Pad25)") (class "Default")
      (node (ref "U2") (pin "25") (pinfunction "D16_/_RX2_25") (pintype "unspecified+no_connect"))
    )
    (net (code "61") (name "unconnected-(U2-D34_{slash}_A2-Pad4)") (class "Default")
      (node (ref "U2") (pin "4") (pinfunction "D34_/_A2_4") (pintype "unspecified+no_connect"))
    )
    (net (code "62") (name "unconnected-(U2-D35_{slash}_A3-Pad5)") (class "Default")
      (node (ref "U2") (pin "5") (pinfunction "D35_/_A3_5") (pintype "unspecified+no_connect"))
    )
    (net (code "63") (name "unconnected-(U2-EN-Pad1)") (class "Default")
      (node (ref "U2") (pin "1") (pinfunction "EN_1") (pintype "unspecified+no_connect"))
    )
    (net (code "64") (name "unconnected-(U2-RXD0{slash}D3_{slash}_RX0-Pad19)") (class "Default")
      (node (ref "U2") (pin "19") (pinfunction "RXD0/D3_/_RX0_19") (pintype "unspecified+no_connect"))
    )
    (net (code "65") (name "unconnected-(U2-TXD0{slash}D1_{slash}_TX0-Pad18)") (class "Default")
      (node (ref "U2") (pin "18") (pinfunction "TXD0/D1_/_TX0_18") (pintype "unspecified+no_connect"))
    )
    (net (code "66") (name "unconnected-(U2-VN_{slash}_A7-Pad3)") (class "Default")
      (node (ref "U2") (pin "3") (pinfunction "VN_/_A7_3") (pintype "unspecified+no_connect"))
    )
    (net (code "67") (name "unconnected-(U2-VP_{slash}_A4-36-Pad2)") (class "Default")
      (node (ref "U2") (pin "2") (pinfunction "VP_/_A4-36_2") (pintype "unspecified+no_connect"))
    )
    (net (code "68") (name "unconnected-(U3-HV2-Pad8)") (class "Default")
      (node (ref "U3") (pin "8") (pinfunction "HV2_8") (pintype "unspecified+no_connect"))
    )
    (net (code "69") (name "unconnected-(U3-HV3-Pad11)") (class "Default")
      (node (ref "U3") (pin "11") (pinfunction "HV3_11") (pintype "unspecified+no_connect"))
    )
    (net (code "70") (name "unconnected-(U3-LV2-Pad2)") (class "Default")
      (node (ref "U3") (pin "2") (pinfunction "LV2_2") (pintype "unspecified+no_connect"))
    )
    (net (code "71") (name "unconnected-(U3-LV3-Pad5)") (class "Default")
      (node (ref "U3") (pin "5") (pinfunction "LV3_5") (pintype "unspecified+no_connect"))
    )
  )
)
